# Skematik.net
KiCad netlist of a schematic drawn in EAGLE
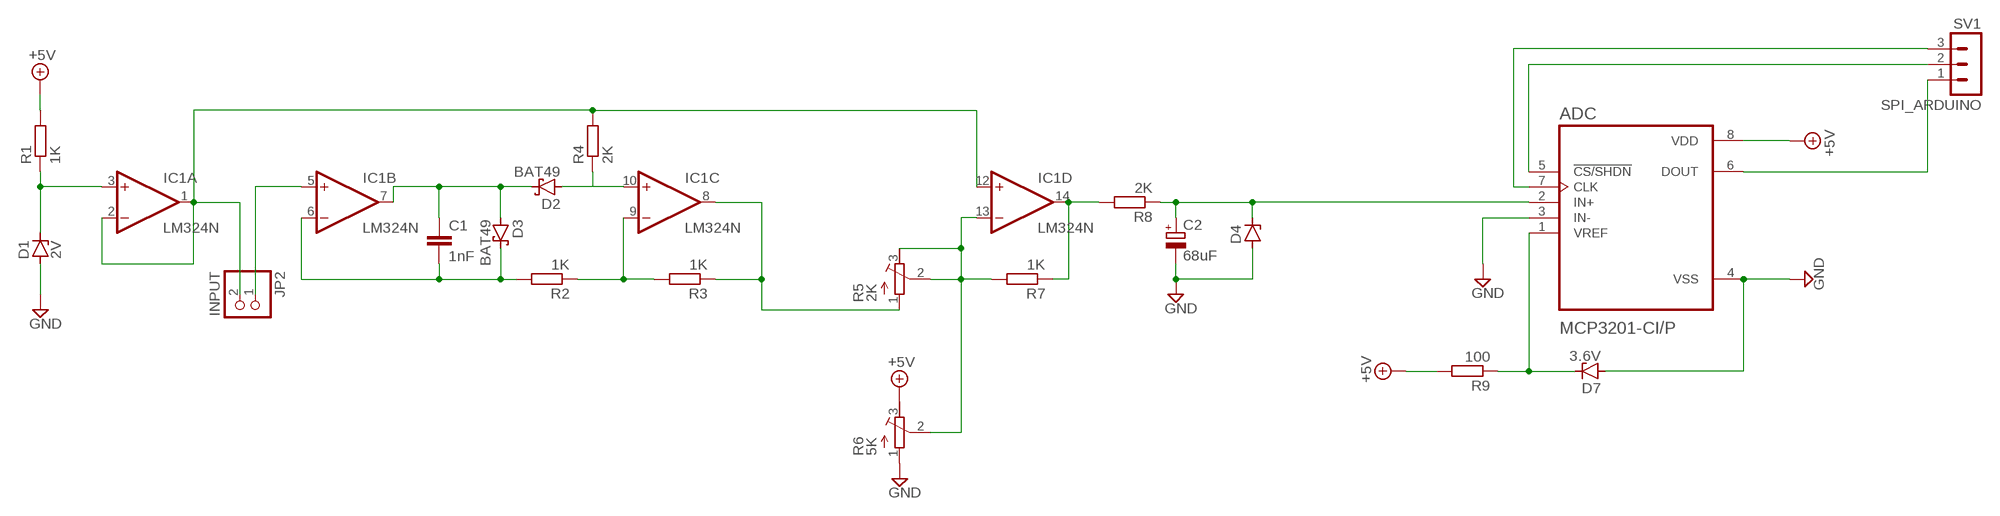
[diagram p0: schematic, sheet 1]

(export (version "E")
  (design (tool "Eeschema 10.0.6"))
  (components
    (comp (ref "ADC")
      (value "MCP3201-CI/P")
      (footprint "eagle-import:DIP787W46P254L927H533Q8")
      (fields (field (name "MF") "Microchip"))
      (libsource (lib "eagle-import") (part "MCP3201-CI/P"))
    )
    (comp (ref "C1")
      (value "1nF")
      (footprint "eagle-import:C025-025X050")
      (libsource (lib "eagle-import") (part "C-EU025-025X050"))
    )
    (comp (ref "C2")
      (value "68uF")
      (footprint "eagle-import:E2-4")
      (libsource (lib "eagle-import") (part "CPOL-EUE2-4"))
    )
    (comp (ref "D1")
      (value "2V")
      (footprint "eagle-import:ZDIO-2.5")
      (libsource (lib "eagle-import") (part "ZENER-DIODEZD-2.5"))
    )
    (comp (ref "D2")
      (value "BAT49")
      (footprint "eagle-import:DO41-10")
      (libsource (lib "eagle-import") (part "BAT49"))
    )
    (comp (ref "D3")
      (value "BAT49")
      (footprint "eagle-import:DO41-10")
      (libsource (lib "eagle-import") (part "BAT49"))
    )
    (comp (ref "D4")
      (value "ZENER-DIODEZD-2.5")
      (footprint "eagle-import:ZDIO-2.5")
      (libsource (lib "eagle-import") (part "ZENER-DIODEZD-2.5"))
    )
    (comp (ref "D7")
      (value "3.6V")
      (footprint "eagle-import:ZDIO-2.5")
      (libsource (lib "eagle-import") (part "ZENER-DIODEZD-2.5"))
    )
    (comp (ref "IC1")
      (value "LM324N")
      (footprint "eagle-import:DIL14")
      (libsource (lib "eagle-import") (part "LM324N"))
    )
    (comp (ref "JP2")
      (value "INPUT")
      (footprint "eagle-import:1X02")
      (libsource (lib "eagle-import") (part "PINHD-1X2"))
    )
    (comp (ref "R1")
      (value "1K")
      (footprint "eagle-import:0204_7")
      (libsource (lib "eagle-import") (part "R-EU_0204/7"))
    )
    (comp (ref "R2")
      (value "1K")
      (footprint "eagle-import:0204_7")
      (libsource (lib "eagle-import") (part "R-EU_0204/7"))
    )
    (comp (ref "R3")
      (value "1K")
      (footprint "eagle-import:0204_7")
      (libsource (lib "eagle-import") (part "R-EU_0204/7"))
    )
    (comp (ref "R4")
      (value "2K")
      (footprint "eagle-import:0204_7")
      (libsource (lib "eagle-import") (part "R-EU_0204/7"))
    )
    (comp (ref "R5")
      (value "2K")
      (footprint "eagle-import:RTRIM64P")
      (libsource (lib "eagle-import") (part "R-TRIMM64P"))
    )
    (comp (ref "R6")
      (value "5K")
      (footprint "eagle-import:RTRIM64P")
      (libsource (lib "eagle-import") (part "R-TRIMM64P"))
    )
    (comp (ref "R7")
      (value "1K")
      (footprint "eagle-import:0204_7")
      (libsource (lib "eagle-import") (part "R-EU_0204/7"))
    )
    (comp (ref "R8")
      (value "2K")
      (footprint "eagle-import:0204_7")
      (libsource (lib "eagle-import") (part "R-EU_0204/7"))
    )
    (comp (ref "R9")
      (value "100")
      (footprint "eagle-import:0204_7")
      (libsource (lib "eagle-import") (part "R-EU_0204/7"))
    )
    (comp (ref "SV1")
      (value "SPI_ARDUINO")
      (footprint "eagle-import:MA03-1")
      (libsource (lib "eagle-import") (part "MA03-1"))
    )
  )
  (nets
    (net (code "1") (name "+5V") (class "Default")
      (node (ref "ADC") (pin "8") (pinfunction "VDD_8") (pintype "power_in"))
      (node (ref "R1") (pin "2") (pinfunction "2_2") (pintype "passive"))
      (node (ref "R6") (pin "3") (pinfunction "E_3") (pintype "passive"))
      (node (ref "R9") (pin "2") (pinfunction "2_2") (pintype "passive"))
    )
    (net (code "2") (name "GND") (class "Default")
      (node (ref "ADC") (pin "3") (pinfunction "IN-_3") (pintype "input"))
      (node (ref "ADC") (pin "4") (pinfunction "VSS_4") (pintype "power_in"))
      (node (ref "C2") (pin "-") (pinfunction "-_-") (pintype "passive"))
      (node (ref "D1") (pin "A") (pinfunction "A_A") (pintype "passive"))
      (node (ref "D4") (pin "A") (pinfunction "A_A") (pintype "passive"))
      (node (ref "D7") (pin "A") (pinfunction "A_A") (pintype "passive"))
      (node (ref "R6") (pin "1") (pinfunction "A_1") (pintype "passive"))
    )
    (net (code "3") (name "Net-(ADC-CLK)") (class "Default")
      (node (ref "ADC") (pin "7") (pinfunction "CLK_7") (pintype "input"))
      (node (ref "SV1") (pin "3") (pinfunction "3_3") (pintype "passive"))
    )
    (net (code "4") (name "Net-(ADC-DOUT)") (class "Default")
      (node (ref "ADC") (pin "6") (pinfunction "DOUT_6") (pintype "output"))
      (node (ref "SV1") (pin "1") (pinfunction "1_1") (pintype "passive"))
    )
    (net (code "5") (name "Net-(ADC-IN+)") (class "Default")
      (node (ref "ADC") (pin "2") (pinfunction "IN+_2") (pintype "input"))
      (node (ref "C2") (pin "+") (pinfunction "+_+") (pintype "passive"))
      (node (ref "D4") (pin "C") (pinfunction "C_C") (pintype "passive"))
      (node (ref "R8") (pin "1") (pinfunction "1_1") (pintype "passive"))
    )
    (net (code "6") (name "Net-(ADC-VREF)") (class "Default")
      (node (ref "ADC") (pin "1") (pinfunction "VREF_1") (pintype "input"))
      (node (ref "D7") (pin "C") (pinfunction "C_C") (pintype "passive"))
      (node (ref "R9") (pin "1") (pinfunction "1_1") (pintype "passive"))
    )
    (net (code "7") (name "Net-(ADC-~{CS{slash}SHDN})") (class "Default")
      (node (ref "ADC") (pin "5") (pinfunction "~{CS/SHDN}_5") (pintype "input"))
      (node (ref "SV1") (pin "2") (pinfunction "2_2") (pintype "passive"))
    )
    (net (code "8") (name "Net-(IC1A-+IN)") (class "Default")
      (node (ref "D1") (pin "C") (pinfunction "C_C") (pintype "passive"))
      (node (ref "IC1") (pin "3") (pinfunction "+IN_3") (pintype "input"))
      (node (ref "R1") (pin "1") (pinfunction "1_1") (pintype "passive"))
    )
    (net (code "9") (name "Net-(IC1A--IN)") (class "Default")
      (node (ref "IC1") (pin "1") (pinfunction "OUT_1") (pintype "output"))
      (node (ref "IC1") (pin "12") (pinfunction "+IN_12") (pintype "input"))
      (node (ref "IC1") (pin "2") (pinfunction "-IN_2") (pintype "input"))
      (node (ref "JP2") (pin "2") (pinfunction "2_2") (pintype "passive"))
      (node (ref "R4") (pin "2") (pinfunction "2_2") (pintype "passive"))
    )
    (net (code "10") (name "Net-(IC1B-+IN)") (class "Default")
      (node (ref "IC1") (pin "5") (pinfunction "+IN_5") (pintype "input"))
      (node (ref "JP2") (pin "1") (pinfunction "1_1") (pintype "passive"))
    )
    (net (code "11") (name "Net-(IC1B--IN)") (class "Default")
      (node (ref "C1") (pin "2") (pinfunction "2_2") (pintype "passive"))
      (node (ref "D3") (pin "C") (pinfunction "C_C") (pintype "passive"))
      (node (ref "IC1") (pin "6") (pinfunction "-IN_6") (pintype "input"))
      (node (ref "R2") (pin "2") (pinfunction "2_2") (pintype "passive"))
    )
    (net (code "12") (name "Net-(IC1B-OUT)") (class "Default")
      (node (ref "C1") (pin "1") (pinfunction "1_1") (pintype "passive"))
      (node (ref "D2") (pin "C") (pinfunction "C_C") (pintype "passive"))
      (node (ref "D3") (pin "A") (pinfunction "A_A") (pintype "passive"))
      (node (ref "IC1") (pin "7") (pinfunction "OUT_7") (pintype "output"))
    )
    (net (code "13") (name "Net-(IC1C-+IN)") (class "Default")
      (node (ref "D2") (pin "A") (pinfunction "A_A") (pintype "passive"))
      (node (ref "IC1") (pin "10") (pinfunction "+IN_10") (pintype "input"))
      (node (ref "R4") (pin "1") (pinfunction "1_1") (pintype "passive"))
    )
    (net (code "14") (name "Net-(IC1C--IN)") (class "Default")
      (node (ref "IC1") (pin "9") (pinfunction "-IN_9") (pintype "input"))
      (node (ref "R2") (pin "1") (pinfunction "1_1") (pintype "passive"))
      (node (ref "R3") (pin "2") (pinfunction "2_2") (pintype "passive"))
    )
    (net (code "15") (name "Net-(IC1C-OUT)") (class "Default")
      (node (ref "IC1") (pin "8") (pinfunction "OUT_8") (pintype "output"))
      (node (ref "R3") (pin "1") (pinfunction "1_1") (pintype "passive"))
      (node (ref "R5") (pin "1") (pinfunction "A_1") (pintype "passive"))
    )
    (net (code "16") (name "Net-(IC1D--IN)") (class "Default")
      (node (ref "IC1") (pin "13") (pinfunction "-IN_13") (pintype "input"))
      (node (ref "R5") (pin "2") (pinfunction "S_2") (pintype "passive"))
      (node (ref "R5") (pin "3") (pinfunction "E_3") (pintype "passive"))
      (node (ref "R6") (pin "2") (pinfunction "S_2") (pintype "passive"))
      (node (ref "R7") (pin "2") (pinfunction "2_2") (pintype "passive"))
    )
    (net (code "17") (name "Net-(IC1D-OUT)") (class "Default")
      (node (ref "IC1") (pin "14") (pinfunction "OUT_14") (pintype "output"))
      (node (ref "R7") (pin "1") (pinfunction "1_1") (pintype "passive"))
      (node (ref "R8") (pin "2") (pinfunction "2_2") (pintype "passive"))
    )
  )
)
